# Esp32_Wroom_Contr_le_d_entr_e.net
KiCad netlist of a schematic drawn in Altium Designer
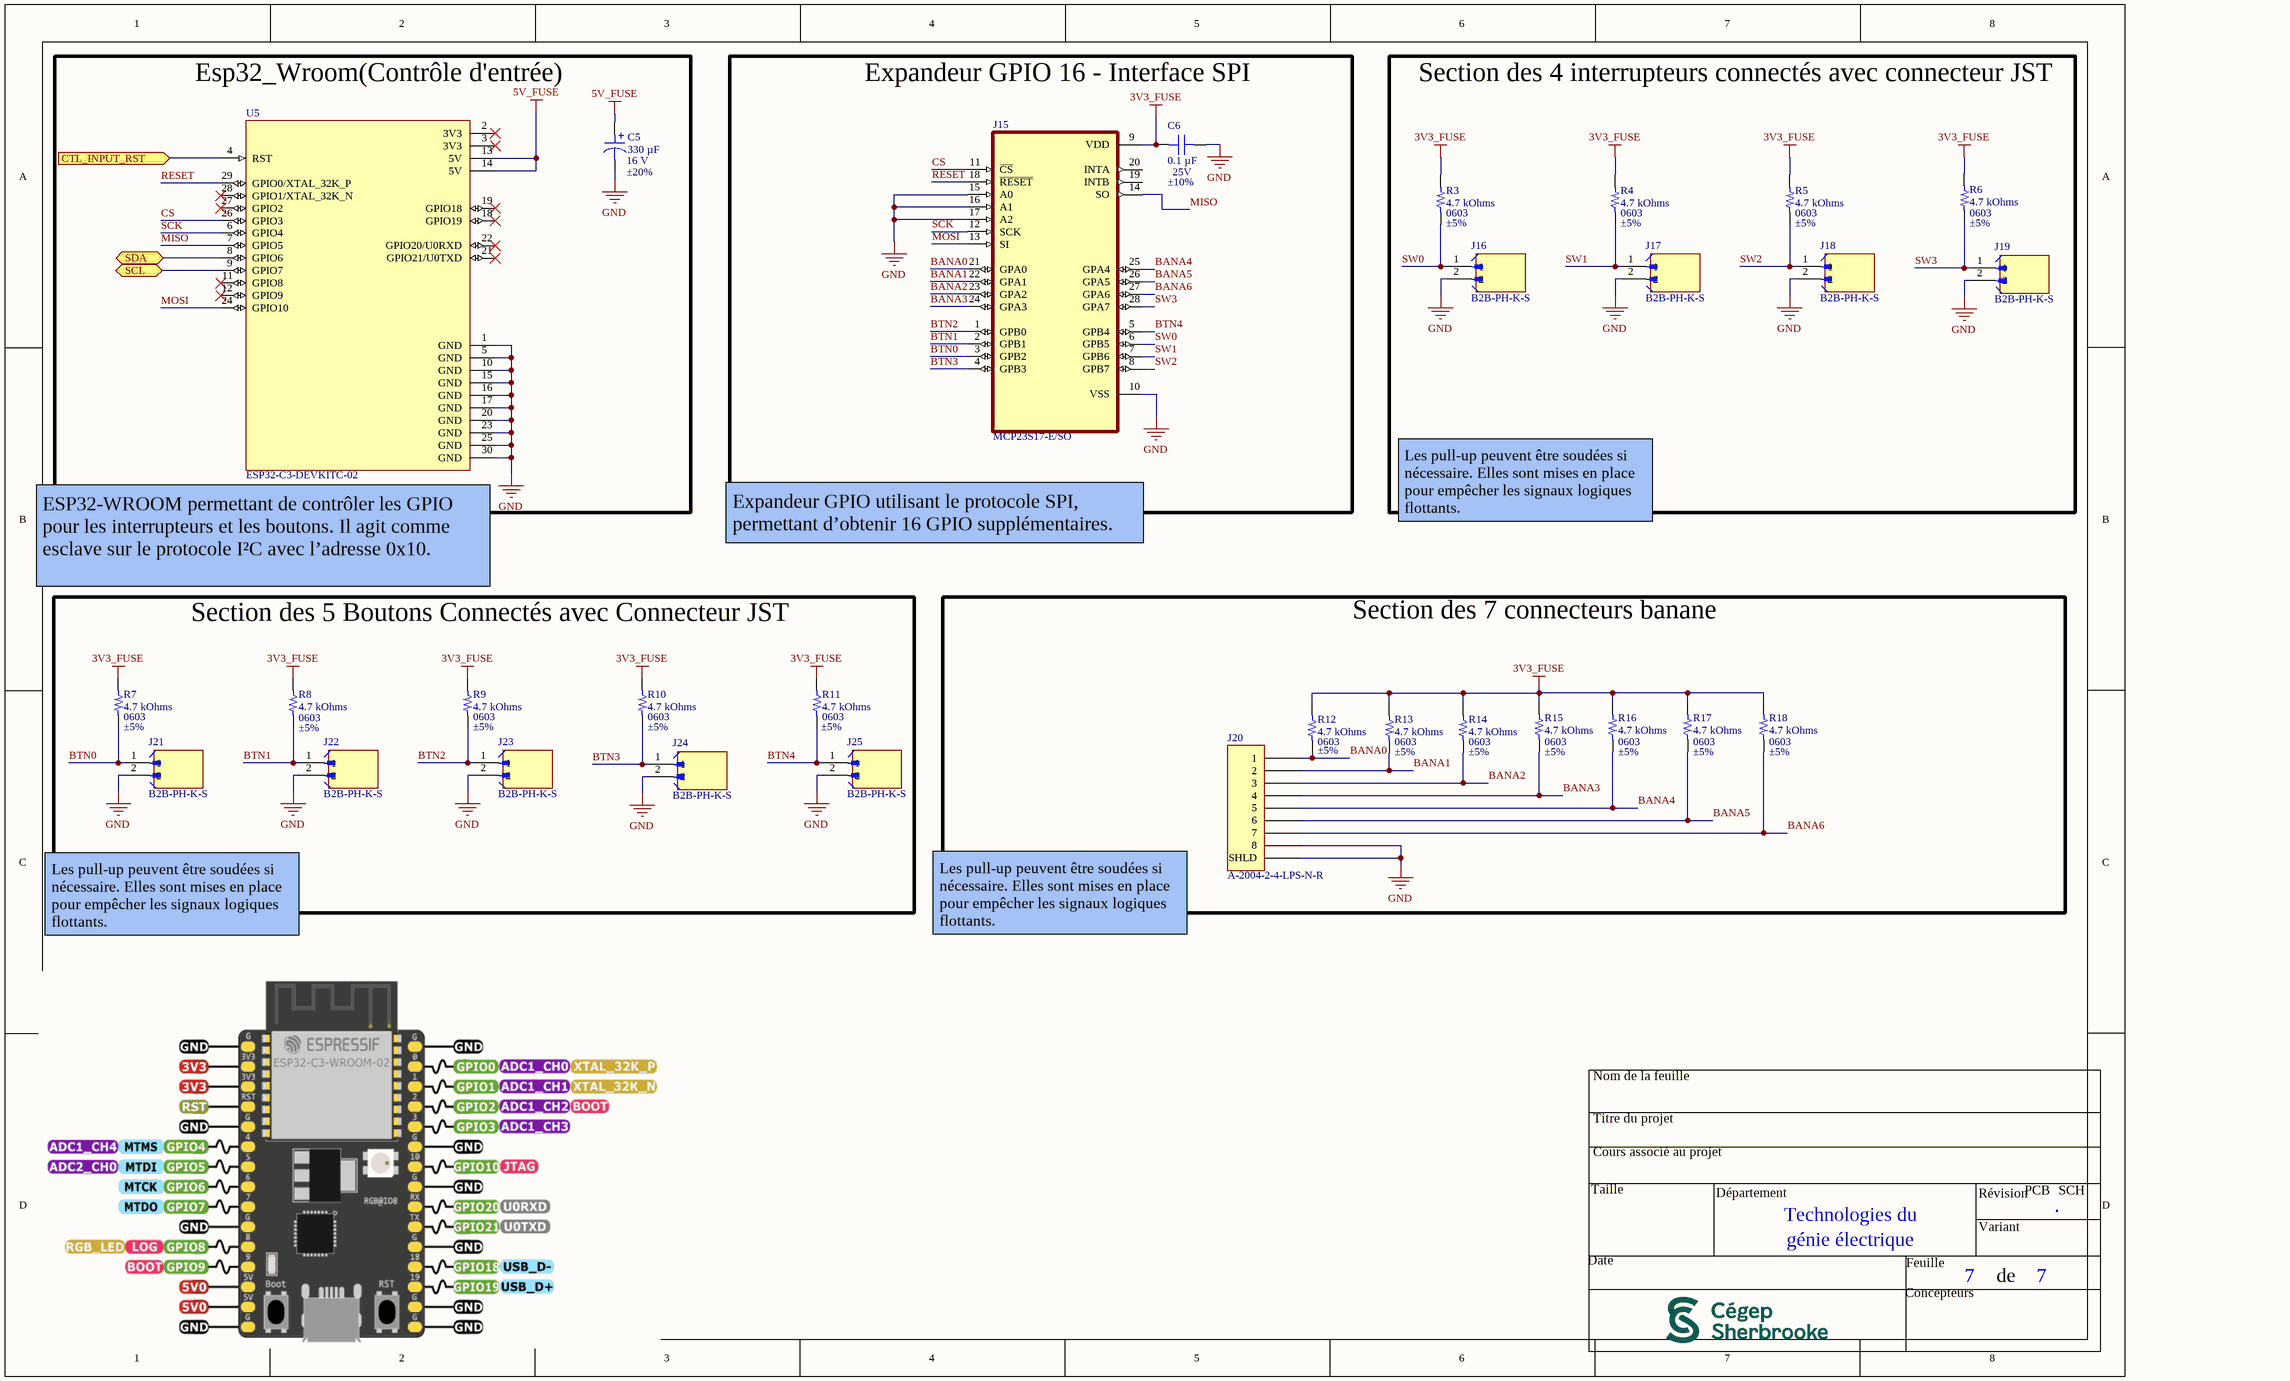
[diagram p0: Esp32_Wroom(Contrôle d'entrée.SchDoc]

(export (version "E")
  (design (tool "Eeschema 10.0.6"))
  (components
    (comp (ref "C5")
      (value "330 µF")
      (footprint "CAP ALSMD 8.3MM H10.5MM")
      (description "CAP ALUM 330UF 20% 16V SMD")
      (fields
        (field (name "PART NUMBER") "865060353008")
        (field (name "MANUFACTURER") "Würth Elektronik")
        (field (name "TOLERANCE") "±20%")
        (field (name "VOLTAGE - RATED") "16 V")
      )
      (libsource (lib "Celestial Altium Library - altium_library") (part "Polarised Capacitor"))
    )
    (comp (ref "C6")
      (value "0.1 µF")
      (footprint "CAP 0805_2012")
      (description "CAP CER 0.1UF 25V X7R 0805")
      (fields
        (field (name "PART NUMBER") "0805Y0250104KXT")
        (field (name "CAPACITANCE") "0.1 µF")
        (field (name "MANUFACTURER") "Knowles Syfer")
        (field (name "TOLERANCE") "±10%")
        (field (name "VOLTAGE - RATED") "25V")
      )
      (libsource (lib "Celestial Altium Library - altium_library") (part "Capacitor"))
    )
    (comp (ref "J15")
      (value "MCP23S17-E/SO")
      (footprint "SOIC127P1030X265-28N")
      (fields (field (name "MF") "Microchip"))
      (libsource (lib "MCP23S17-E_SO") (part "MCP23S17-E/SO"))
    )
    (comp (ref "J16")
      (value "B2B-PH-K-S")
      (footprint "JST_B2B-PH-K-S")
      (description "Connector Header Through Hole 2 position 0.079 (2.00mm)")
      (fields (field (name "MF") "JST Sales America Inc."))
      (libsource (lib "B2B-PH-K-S") (part "B2B-PH-K-S"))
    )
    (comp (ref "J17")
      (value "B2B-PH-K-S")
      (footprint "JST_B2B-PH-K-S")
      (description "Connector Header Through Hole 2 position 0.079 (2.00mm)")
      (fields (field (name "MF") "JST Sales America Inc."))
      (libsource (lib "B2B-PH-K-S") (part "B2B-PH-K-S"))
    )
    (comp (ref "J18")
      (value "B2B-PH-K-S")
      (footprint "JST_B2B-PH-K-S")
      (description "Connector Header Through Hole 2 position 0.079 (2.00mm)")
      (fields (field (name "MF") "JST Sales America Inc."))
      (libsource (lib "B2B-PH-K-S") (part "B2B-PH-K-S"))
    )
    (comp (ref "J19")
      (value "B2B-PH-K-S")
      (footprint "JST_B2B-PH-K-S")
      (description "Connector Header Through Hole 2 position 0.079 (2.00mm)")
      (fields (field (name "MF") "JST Sales America Inc."))
      (libsource (lib "B2B-PH-K-S") (part "B2B-PH-K-S"))
    )
    (comp (ref "J20")
      (value "A-2004-2-4-LPS-N-R")
      (footprint "ASSMANN A-2004-2-4-LPS-N-R")
      (description "CONN MOD JACK 8P8C R/A SHIELDED")
      (fields (field (name "MANUFACTURER") "Assmann WSW Components"))
      (libsource (lib "Celestial Altium Library - altium_library") (part "Modular Jack with Shield"))
    )
    (comp (ref "J21")
      (value "B2B-PH-K-S")
      (footprint "JST_B2B-PH-K-S")
      (description "Connector Header Through Hole 2 position 0.079 (2.00mm)")
      (fields (field (name "MF") "JST Sales America Inc."))
      (libsource (lib "B2B-PH-K-S") (part "B2B-PH-K-S"))
    )
    (comp (ref "J22")
      (value "B2B-PH-K-S")
      (footprint "JST_B2B-PH-K-S")
      (description "Connector Header Through Hole 2 position 0.079 (2.00mm)")
      (fields (field (name "MF") "JST Sales America Inc."))
      (libsource (lib "B2B-PH-K-S") (part "B2B-PH-K-S"))
    )
    (comp (ref "J23")
      (value "B2B-PH-K-S")
      (footprint "JST_B2B-PH-K-S")
      (description "Connector Header Through Hole 2 position 0.079 (2.00mm)")
      (fields (field (name "MF") "JST Sales America Inc."))
      (libsource (lib "B2B-PH-K-S") (part "B2B-PH-K-S"))
    )
    (comp (ref "J24")
      (value "B2B-PH-K-S")
      (footprint "JST_B2B-PH-K-S")
      (description "Connector Header Through Hole 2 position 0.079 (2.00mm)")
      (fields (field (name "MF") "JST Sales America Inc."))
      (libsource (lib "B2B-PH-K-S") (part "B2B-PH-K-S"))
    )
    (comp (ref "J25")
      (value "B2B-PH-K-S")
      (footprint "JST_B2B-PH-K-S")
      (description "Connector Header Through Hole 2 position 0.079 (2.00mm)")
      (fields (field (name "MF") "JST Sales America Inc."))
      (libsource (lib "B2B-PH-K-S") (part "B2B-PH-K-S"))
    )
    (comp (ref "R3")
      (value "4.7 kOhms")
      (footprint "RES 0603_1608")
      (description "RES SMD 4.7K OHM 5% 1/4W 0603")
      (fields
        (field (name "PART NUMBER") "ESR03EZPJ472")
        (field (name "MANUFACTURER") "Rohm Semiconductor")
        (field (name "SUPPLIER DEVICE PACKAGE") "0603")
        (field (name "TOLERANCE") "±5%")
      )
      (libsource (lib "Celestial Altium Library - altium_library") (part "Resistor"))
    )
    (comp (ref "R4")
      (value "4.7 kOhms")
      (footprint "RES 0603_1608")
      (description "RES SMD 4.7K OHM 5% 1/4W 0603")
      (fields
        (field (name "PART NUMBER") "ESR03EZPJ472")
        (field (name "MANUFACTURER") "Rohm Semiconductor")
        (field (name "SUPPLIER DEVICE PACKAGE") "0603")
        (field (name "TOLERANCE") "±5%")
      )
      (libsource (lib "Celestial Altium Library - altium_library") (part "Resistor"))
    )
    (comp (ref "R5")
      (value "4.7 kOhms")
      (footprint "RES 0603_1608")
      (description "RES SMD 4.7K OHM 5% 1/4W 0603")
      (fields
        (field (name "PART NUMBER") "ESR03EZPJ472")
        (field (name "MANUFACTURER") "Rohm Semiconductor")
        (field (name "SUPPLIER DEVICE PACKAGE") "0603")
        (field (name "TOLERANCE") "±5%")
      )
      (libsource (lib "Celestial Altium Library - altium_library") (part "Resistor"))
    )
    (comp (ref "R6")
      (value "4.7 kOhms")
      (footprint "RES 0603_1608")
      (description "RES SMD 4.7K OHM 5% 1/4W 0603")
      (fields
        (field (name "PART NUMBER") "ESR03EZPJ472")
        (field (name "MANUFACTURER") "Rohm Semiconductor")
        (field (name "SUPPLIER DEVICE PACKAGE") "0603")
        (field (name "TOLERANCE") "±5%")
      )
      (libsource (lib "Celestial Altium Library - altium_library") (part "Resistor"))
    )
    (comp (ref "R7")
      (value "4.7 kOhms")
      (footprint "RES 0603_1608")
      (description "RES SMD 4.7K OHM 5% 1/4W 0603")
      (fields
        (field (name "PART NUMBER") "ESR03EZPJ472")
        (field (name "MANUFACTURER") "Rohm Semiconductor")
        (field (name "SUPPLIER DEVICE PACKAGE") "0603")
        (field (name "TOLERANCE") "±5%")
      )
      (libsource (lib "Celestial Altium Library - altium_library") (part "Resistor"))
    )
    (comp (ref "R8")
      (value "4.7 kOhms")
      (footprint "RES 0603_1608")
      (description "RES SMD 4.7K OHM 5% 1/4W 0603")
      (fields
        (field (name "PART NUMBER") "ESR03EZPJ472")
        (field (name "MANUFACTURER") "Rohm Semiconductor")
        (field (name "SUPPLIER DEVICE PACKAGE") "0603")
        (field (name "TOLERANCE") "±5%")
      )
      (libsource (lib "Celestial Altium Library - altium_library") (part "Resistor"))
    )
    (comp (ref "R9")
      (value "4.7 kOhms")
      (footprint "RES 0603_1608")
      (description "RES SMD 4.7K OHM 5% 1/4W 0603")
      (fields
        (field (name "PART NUMBER") "ESR03EZPJ472")
        (field (name "MANUFACTURER") "Rohm Semiconductor")
        (field (name "SUPPLIER DEVICE PACKAGE") "0603")
        (field (name "TOLERANCE") "±5%")
      )
      (libsource (lib "Celestial Altium Library - altium_library") (part "Resistor"))
    )
    (comp (ref "R10")
      (value "4.7 kOhms")
      (footprint "RES 0603_1608")
      (description "RES SMD 4.7K OHM 5% 1/4W 0603")
      (fields
        (field (name "PART NUMBER") "ESR03EZPJ472")
        (field (name "MANUFACTURER") "Rohm Semiconductor")
        (field (name "SUPPLIER DEVICE PACKAGE") "0603")
        (field (name "TOLERANCE") "±5%")
      )
      (libsource (lib "Celestial Altium Library - altium_library") (part "Resistor"))
    )
    (comp (ref "R11")
      (value "4.7 kOhms")
      (footprint "RES 0603_1608")
      (description "RES SMD 4.7K OHM 5% 1/4W 0603")
      (fields
        (field (name "PART NUMBER") "ESR03EZPJ472")
        (field (name "MANUFACTURER") "Rohm Semiconductor")
        (field (name "SUPPLIER DEVICE PACKAGE") "0603")
        (field (name "TOLERANCE") "±5%")
      )
      (libsource (lib "Celestial Altium Library - altium_library") (part "Resistor"))
    )
    (comp (ref "R12")
      (value "4.7 kOhms")
      (footprint "RES 0603_1608")
      (description "RES SMD 4.7K OHM 5% 1/4W 0603")
      (fields
        (field (name "PART NUMBER") "ESR03EZPJ472")
        (field (name "MANUFACTURER") "Rohm Semiconductor")
        (field (name "SUPPLIER DEVICE PACKAGE") "0603")
        (field (name "TOLERANCE") "±5%")
      )
      (libsource (lib "Celestial Altium Library - altium_library") (part "Resistor"))
    )
    (comp (ref "R13")
      (value "4.7 kOhms")
      (footprint "RES 0603_1608")
      (description "RES SMD 4.7K OHM 5% 1/4W 0603")
      (fields
        (field (name "PART NUMBER") "ESR03EZPJ472")
        (field (name "MANUFACTURER") "Rohm Semiconductor")
        (field (name "SUPPLIER DEVICE PACKAGE") "0603")
        (field (name "TOLERANCE") "±5%")
      )
      (libsource (lib "Celestial Altium Library - altium_library") (part "Resistor"))
    )
    (comp (ref "R14")
      (value "4.7 kOhms")
      (footprint "RES 0603_1608")
      (description "RES SMD 4.7K OHM 5% 1/4W 0603")
      (fields
        (field (name "PART NUMBER") "ESR03EZPJ472")
        (field (name "MANUFACTURER") "Rohm Semiconductor")
        (field (name "SUPPLIER DEVICE PACKAGE") "0603")
        (field (name "TOLERANCE") "±5%")
      )
      (libsource (lib "Celestial Altium Library - altium_library") (part "Resistor"))
    )
    (comp (ref "R15")
      (value "4.7 kOhms")
      (footprint "RES 0603_1608")
      (description "RES SMD 4.7K OHM 5% 1/4W 0603")
      (fields
        (field (name "PART NUMBER") "ESR03EZPJ472")
        (field (name "MANUFACTURER") "Rohm Semiconductor")
        (field (name "SUPPLIER DEVICE PACKAGE") "0603")
        (field (name "TOLERANCE") "±5%")
      )
      (libsource (lib "Celestial Altium Library - altium_library") (part "Resistor"))
    )
    (comp (ref "R16")
      (value "4.7 kOhms")
      (footprint "RES 0603_1608")
      (description "RES SMD 4.7K OHM 5% 1/4W 0603")
      (fields
        (field (name "PART NUMBER") "ESR03EZPJ472")
        (field (name "MANUFACTURER") "Rohm Semiconductor")
        (field (name "SUPPLIER DEVICE PACKAGE") "0603")
        (field (name "TOLERANCE") "±5%")
      )
      (libsource (lib "Celestial Altium Library - altium_library") (part "Resistor"))
    )
    (comp (ref "R17")
      (value "4.7 kOhms")
      (footprint "RES 0603_1608")
      (description "RES SMD 4.7K OHM 5% 1/4W 0603")
      (fields
        (field (name "PART NUMBER") "ESR03EZPJ472")
        (field (name "MANUFACTURER") "Rohm Semiconductor")
        (field (name "SUPPLIER DEVICE PACKAGE") "0603")
        (field (name "TOLERANCE") "±5%")
      )
      (libsource (lib "Celestial Altium Library - altium_library") (part "Resistor"))
    )
    (comp (ref "R18")
      (value "4.7 kOhms")
      (footprint "RES 0603_1608")
      (description "RES SMD 4.7K OHM 5% 1/4W 0603")
      (fields
        (field (name "PART NUMBER") "ESR03EZPJ472")
        (field (name "MANUFACTURER") "Rohm Semiconductor")
        (field (name "SUPPLIER DEVICE PACKAGE") "0603")
        (field (name "TOLERANCE") "±5%")
      )
      (libsource (lib "Celestial Altium Library - altium_library") (part "Resistor"))
    )
    (comp (ref "U5")
      (value "ESP32-C3-DEVKITC-02")
      (footprint "XCVR_ESP32-C3-DEVKITC-02")
      (fields (field (name "MF") "Espressif Systems") (field (name "MP") "ESP32-C3-DevKitC-02"))
      (libsource (lib "ESP32-C3-DEVKITC-02") (part "ESP32-C3-DEVKITC-02"))
    )
  )
  (nets
    (net (code "1") (name "/BANA0") (class "Default")
      (node (ref "J15") (pin "21") (pinfunction "GPA0_21") (pintype "bidirectional"))
      (node (ref "J20") (pin "1") (pinfunction "1_1") (pintype "passive"))
      (node (ref "R12") (pin "1") (pinfunction "1_1") (pintype "passive"))
    )
    (net (code "2") (name "/BANA1") (class "Default")
      (node (ref "J15") (pin "22") (pinfunction "GPA1_22") (pintype "bidirectional"))
      (node (ref "J20") (pin "2") (pinfunction "2_2") (pintype "passive"))
      (node (ref "R13") (pin "1") (pinfunction "1_1") (pintype "passive"))
    )
    (net (code "3") (name "/BANA2") (class "Default")
      (node (ref "J15") (pin "23") (pinfunction "GPA2_23") (pintype "bidirectional"))
      (node (ref "J20") (pin "3") (pinfunction "3_3") (pintype "passive"))
      (node (ref "R14") (pin "1") (pinfunction "1_1") (pintype "passive"))
    )
    (net (code "4") (name "/BANA3") (class "Default")
      (node (ref "J15") (pin "24") (pinfunction "GPA3_24") (pintype "bidirectional"))
      (node (ref "J20") (pin "4") (pinfunction "4_4") (pintype "passive"))
      (node (ref "R15") (pin "1") (pinfunction "1_1") (pintype "passive"))
    )
    (net (code "5") (name "/BANA4") (class "Default")
      (node (ref "J15") (pin "25") (pinfunction "GPA4_25") (pintype "bidirectional"))
      (node (ref "J20") (pin "5") (pinfunction "5_5") (pintype "passive"))
      (node (ref "R16") (pin "1") (pinfunction "1_1") (pintype "passive"))
    )
    (net (code "6") (name "/BANA5") (class "Default")
      (node (ref "J15") (pin "26") (pinfunction "GPA5_26") (pintype "bidirectional"))
      (node (ref "J20") (pin "6") (pinfunction "6_6") (pintype "passive"))
      (node (ref "R17") (pin "1") (pinfunction "1_1") (pintype "passive"))
    )
    (net (code "7") (name "/BANA6") (class "Default")
      (node (ref "J15") (pin "27") (pinfunction "GPA6_27") (pintype "bidirectional"))
      (node (ref "J20") (pin "7") (pinfunction "7_7") (pintype "passive"))
      (node (ref "R18") (pin "1") (pinfunction "1_1") (pintype "passive"))
    )
    (net (code "8") (name "/BTN0") (class "Default")
      (node (ref "J15") (pin "3") (pinfunction "GPB2_3") (pintype "bidirectional"))
      (node (ref "J21") (pin "1") (pinfunction "1_1") (pintype "passive"))
      (node (ref "R7") (pin "1") (pinfunction "1_1") (pintype "passive"))
    )
    (net (code "9") (name "/BTN1") (class "Default")
      (node (ref "J15") (pin "2") (pinfunction "GPB1_2") (pintype "bidirectional"))
      (node (ref "J22") (pin "1") (pinfunction "1_1") (pintype "passive"))
      (node (ref "R8") (pin "1") (pinfunction "1_1") (pintype "passive"))
    )
    (net (code "10") (name "/BTN2") (class "Default")
      (node (ref "J15") (pin "1") (pinfunction "GPB0_1") (pintype "bidirectional"))
      (node (ref "J23") (pin "1") (pinfunction "1_1") (pintype "passive"))
      (node (ref "R9") (pin "1") (pinfunction "1_1") (pintype "passive"))
    )
    (net (code "11") (name "/BTN3") (class "Default")
      (node (ref "J15") (pin "4") (pinfunction "GPB3_4") (pintype "bidirectional"))
      (node (ref "J24") (pin "1") (pinfunction "1_1") (pintype "passive"))
      (node (ref "R10") (pin "1") (pinfunction "1_1") (pintype "passive"))
    )
    (net (code "12") (name "/BTN4") (class "Default")
      (node (ref "J15") (pin "5") (pinfunction "GPB4_5") (pintype "bidirectional"))
      (node (ref "J25") (pin "1") (pinfunction "1_1") (pintype "passive"))
      (node (ref "R11") (pin "1") (pinfunction "1_1") (pintype "passive"))
    )
    (net (code "13") (name "/CS") (class "Default")
      (node (ref "J15") (pin "11") (pinfunction "~{CS}_11") (pintype "input"))
      (node (ref "U5") (pin "26") (pinfunction "GPIO3_26") (pintype "bidirectional"))
    )
    (net (code "14") (name "/CTL_INPUT_RST") (class "Default")
      (node (ref "U5") (pin "4") (pinfunction "RST_4") (pintype "input"))
    )
    (net (code "15") (name "/MISO") (class "Default")
      (node (ref "J15") (pin "14") (pinfunction "SO_14") (pintype "output"))
      (node (ref "U5") (pin "7") (pinfunction "GPIO5_7") (pintype "bidirectional"))
    )
    (net (code "16") (name "/MOSI") (class "Default")
      (node (ref "J15") (pin "13") (pinfunction "SI_13") (pintype "input"))
      (node (ref "U5") (pin "24") (pinfunction "GPIO10_24") (pintype "bidirectional"))
    )
    (net (code "17") (name "/RESET") (class "Default")
      (node (ref "J15") (pin "18") (pinfunction "~{RESET}_18") (pintype "input"))
      (node (ref "U5") (pin "29") (pinfunction "GPIO0/XTAL_32K_P_29") (pintype "bidirectional"))
    )
    (net (code "18") (name "/SCK") (class "Default")
      (node (ref "J15") (pin "12") (pinfunction "SCK_12") (pintype "input"))
      (node (ref "U5") (pin "6") (pinfunction "GPIO4_6") (pintype "bidirectional"))
    )
    (net (code "19") (name "/SCL") (class "Default")
      (node (ref "U5") (pin "9") (pinfunction "GPIO7_9") (pintype "bidirectional"))
    )
    (net (code "20") (name "/SDA") (class "Default")
      (node (ref "U5") (pin "8") (pinfunction "GPIO6_8") (pintype "bidirectional"))
    )
    (net (code "21") (name "/SW0") (class "Default")
      (node (ref "J15") (pin "6") (pinfunction "GPB5_6") (pintype "bidirectional"))
      (node (ref "J16") (pin "1") (pinfunction "1_1") (pintype "passive"))
      (node (ref "R3") (pin "1") (pinfunction "1_1") (pintype "passive"))
    )
    (net (code "22") (name "/SW1") (class "Default")
      (node (ref "J15") (pin "7") (pinfunction "GPB6_7") (pintype "bidirectional"))
      (node (ref "J17") (pin "1") (pinfunction "1_1") (pintype "passive"))
      (node (ref "R4") (pin "1") (pinfunction "1_1") (pintype "passive"))
    )
    (net (code "23") (name "/SW2") (class "Default")
      (node (ref "J15") (pin "8") (pinfunction "GPB7_8") (pintype "bidirectional"))
      (node (ref "J18") (pin "1") (pinfunction "1_1") (pintype "passive"))
      (node (ref "R5") (pin "1") (pinfunction "1_1") (pintype "passive"))
    )
    (net (code "24") (name "/SW3") (class "Default")
      (node (ref "J15") (pin "28") (pinfunction "GPA7_28") (pintype "bidirectional"))
      (node (ref "J19") (pin "1") (pinfunction "1_1") (pintype "passive"))
      (node (ref "R6") (pin "1") (pinfunction "1_1") (pintype "passive"))
    )
    (net (code "25") (name "3V3_FUSE") (class "Default")
      (node (ref "C6") (pin "1") (pinfunction "1_1") (pintype "passive"))
      (node (ref "J15") (pin "9") (pinfunction "VDD_9") (pintype "power_in"))
      (node (ref "R10") (pin "2") (pinfunction "2_2") (pintype "passive"))
      (node (ref "R11") (pin "2") (pinfunction "2_2") (pintype "passive"))
      (node (ref "R12") (pin "2") (pinfunction "2_2") (pintype "passive"))
      (node (ref "R13") (pin "2") (pinfunction "2_2") (pintype "passive"))
      (node (ref "R14") (pin "2") (pinfunction "2_2") (pintype "passive"))
      (node (ref "R15") (pin "2") (pinfunction "2_2") (pintype "passive"))
      (node (ref "R16") (pin "2") (pinfunction "2_2") (pintype "passive"))
      (node (ref "R17") (pin "2") (pinfunction "2_2") (pintype "passive"))
      (node (ref "R18") (pin "2") (pinfunction "2_2") (pintype "passive"))
      (node (ref "R3") (pin "2") (pinfunction "2_2") (pintype "passive"))
      (node (ref "R4") (pin "2") (pinfunction "2_2") (pintype "passive"))
      (node (ref "R5") (pin "2") (pinfunction "2_2") (pintype "passive"))
      (node (ref "R6") (pin "2") (pinfunction "2_2") (pintype "passive"))
      (node (ref "R7") (pin "2") (pinfunction "2_2") (pintype "passive"))
      (node (ref "R8") (pin "2") (pinfunction "2_2") (pintype "passive"))
      (node (ref "R9") (pin "2") (pinfunction "2_2") (pintype "passive"))
    )
    (net (code "26") (name "5V_FUSE") (class "Default")
      (node (ref "C5") (pin "1") (pinfunction "1_1") (pintype "passive"))
      (node (ref "U5") (pin "13") (pinfunction "5V_13") (pintype "power_in"))
      (node (ref "U5") (pin "14") (pinfunction "5V_14") (pintype "power_in"))
    )
    (net (code "27") (name "GND") (class "Default")
      (node (ref "C5") (pin "2") (pinfunction "2_2") (pintype "passive"))
      (node (ref "C6") (pin "2") (pinfunction "2_2") (pintype "passive"))
      (node (ref "J15") (pin "10") (pinfunction "VSS_10") (pintype "power_in"))
      (node (ref "J15") (pin "15") (pinfunction "A0_15") (pintype "input"))
      (node (ref "J15") (pin "16") (pinfunction "A1_16") (pintype "input"))
      (node (ref "J15") (pin "17") (pinfunction "A2_17") (pintype "input"))
      (node (ref "J16") (pin "2") (pinfunction "2_2") (pintype "passive"))
      (node (ref "J17") (pin "2") (pinfunction "2_2") (pintype "passive"))
      (node (ref "J18") (pin "2") (pinfunction "2_2") (pintype "passive"))
      (node (ref "J19") (pin "2") (pinfunction "2_2") (pintype "passive"))
      (node (ref "J20") (pin "8") (pinfunction "8_8") (pintype "passive"))
      (node (ref "J20") (pin "S") (pinfunction "SHLD_S") (pintype "passive"))
      (node (ref "J21") (pin "2") (pinfunction "2_2") (pintype "passive"))
      (node (ref "J22") (pin "2") (pinfunction "2_2") (pintype "passive"))
      (node (ref "J23") (pin "2") (pinfunction "2_2") (pintype "passive"))
      (node (ref "J24") (pin "2") (pinfunction "2_2") (pintype "passive"))
      (node (ref "J25") (pin "2") (pinfunction "2_2") (pintype "passive"))
      (node (ref "U5") (pin "1") (pinfunction "GND_1") (pintype "power_in"))
      (node (ref "U5") (pin "10") (pinfunction "GND_10") (pintype "power_in"))
      (node (ref "U5") (pin "15") (pinfunction "GND_15") (pintype "power_in"))
      (node (ref "U5") (pin "16") (pinfunction "GND_16") (pintype "power_in"))
      (node (ref "U5") (pin "17") (pinfunction "GND_17") (pintype "power_in"))
      (node (ref "U5") (pin "20") (pinfunction "GND_20") (pintype "power_in"))
      (node (ref "U5") (pin "23") (pinfunction "GND_23") (pintype "power_in"))
      (node (ref "U5") (pin "25") (pinfunction "GND_25") (pintype "power_in"))
      (node (ref "U5") (pin "30") (pinfunction "GND_30") (pintype "power_in"))
      (node (ref "U5") (pin "5") (pinfunction "GND_5") (pintype "power_in"))
    )
    (net (code "28") (name "unconnected-(J15-INTA-Pad20)") (class "Default")
      (node (ref "J15") (pin "20") (pinfunction "INTA_20") (pintype "output"))
    )
    (net (code "29") (name "unconnected-(J15-INTB-Pad19)") (class "Default")
      (node (ref "J15") (pin "19") (pinfunction "INTB_19") (pintype "output"))
    )
    (net (code "30") (name "unconnected-(U5-3V3-Pad2)") (class "Default")
      (node (ref "U5") (pin "2") (pinfunction "3V3_2") (pintype "power_in+no_connect"))
    )
    (net (code "31") (name "unconnected-(U5-3V3-Pad3)") (class "Default")
      (node (ref "U5") (pin "3") (pinfunction "3V3_3") (pintype "power_in+no_connect"))
    )
    (net (code "32") (name "unconnected-(U5-GPIO1{slash}XTAL_32K_N-Pad28)") (class "Default")
      (node (ref "U5") (pin "28") (pinfunction "GPIO1/XTAL_32K_N_28") (pintype "bidirectional+no_connect"))
    )
    (net (code "33") (name "unconnected-(U5-GPIO2-Pad27)") (class "Default")
      (node (ref "U5") (pin "27") (pinfunction "GPIO2_27") (pintype "bidirectional+no_connect"))
    )
    (net (code "34") (name "unconnected-(U5-GPIO8-Pad11)") (class "Default")
      (node (ref "U5") (pin "11") (pinfunction "GPIO8_11") (pintype "bidirectional+no_connect"))
    )
    (net (code "35") (name "unconnected-(U5-GPIO9-Pad12)") (class "Default")
      (node (ref "U5") (pin "12") (pinfunction "GPIO9_12") (pintype "bidirectional+no_connect"))
    )
    (net (code "36") (name "unconnected-(U5-GPIO18-Pad19)") (class "Default")
      (node (ref "U5") (pin "19") (pinfunction "GPIO18_19") (pintype "bidirectional+no_connect"))
    )
    (net (code "37") (name "unconnected-(U5-GPIO19-Pad18)") (class "Default")
      (node (ref "U5") (pin "18") (pinfunction "GPIO19_18") (pintype "bidirectional+no_connect"))
    )
    (net (code "38") (name "unconnected-(U5-GPIO20{slash}U0RXD-Pad22)") (class "Default")
      (node (ref "U5") (pin "22") (pinfunction "GPIO20/U0RXD_22") (pintype "bidirectional+no_connect"))
    )
    (net (code "39") (name "unconnected-(U5-GPIO21{slash}U0TXD-Pad21)") (class "Default")
      (node (ref "U5") (pin "21") (pinfunction "GPIO21/U0TXD_21") (pintype "bidirectional+no_connect"))
    )
  )
)
